# PCB1a_Adapter.net
KiCad netlist of a schematic drawn in EAGLE
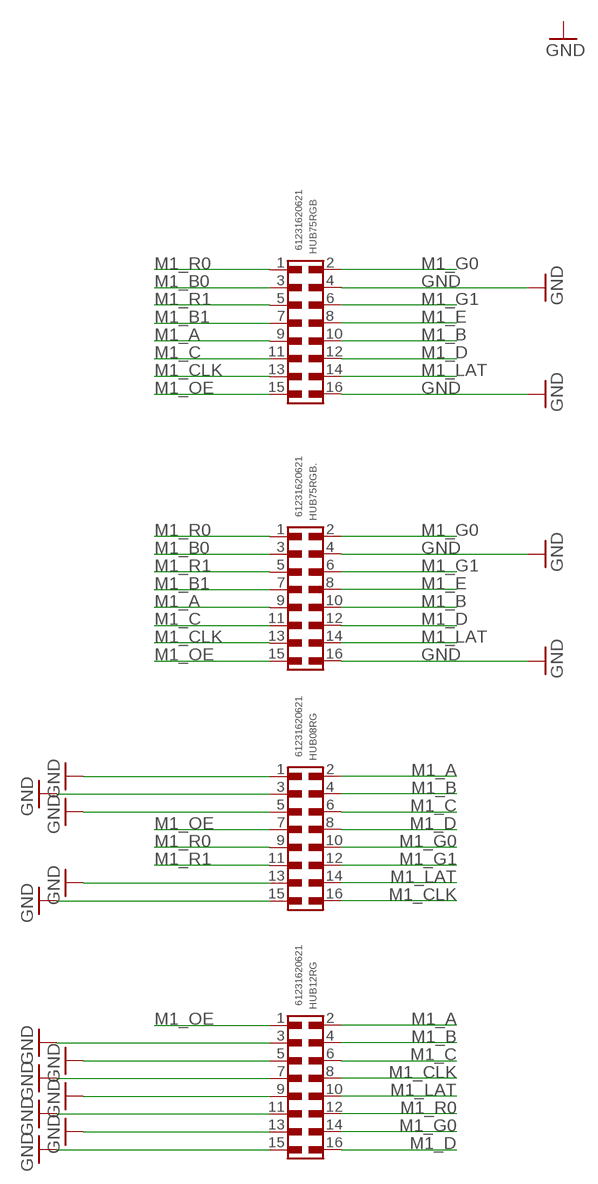
[diagram p0: schematic, sheet 1]

(export (version "E")
  (design (tool "Eeschema 10.0.6"))
  (components
    (comp (ref "HUB08RG")
      (value "61231620621")
      (footprint "eagle-import:61231620621")
      (libsource (lib "eagle-import") (part "6123XX20621_61231620621"))
    )
    (comp (ref "HUB12RG")
      (value "61231620621")
      (footprint "eagle-import:61231620621")
      (libsource (lib "eagle-import") (part "6123XX20621_61231620621"))
    )
    (comp (ref "HUB75RGB")
      (value "61231620621")
      (footprint "eagle-import:61231620621")
      (libsource (lib "eagle-import") (part "6123XX20621_61231620621"))
    )
    (comp (ref "HUB75RGB.")
      (value "61231620621")
      (footprint "eagle-import:61231620621")
      (libsource (lib "eagle-import") (part "6123XX20621_61231620621"))
    )
  )
  (nets
    (net (code "1") (name "/M1_A") (class "Default")
      (node (ref "HUB08RG") (pin "2") (pinfunction "2_2") (pintype "passive"))
      (node (ref "HUB12RG") (pin "2") (pinfunction "2_2") (pintype "passive"))
      (node (ref "HUB75RGB") (pin "9") (pinfunction "9_9") (pintype "passive"))
      (node (ref "HUB75RGB.") (pin "9") (pinfunction "9_9") (pintype "passive"))
    )
    (net (code "2") (name "/M1_B") (class "Default")
      (node (ref "HUB08RG") (pin "4") (pinfunction "4_4") (pintype "passive"))
      (node (ref "HUB12RG") (pin "4") (pinfunction "4_4") (pintype "passive"))
      (node (ref "HUB75RGB") (pin "10") (pinfunction "10_10") (pintype "passive"))
      (node (ref "HUB75RGB.") (pin "10") (pinfunction "10_10") (pintype "passive"))
    )
    (net (code "3") (name "/M1_B0") (class "Default")
      (node (ref "HUB75RGB") (pin "3") (pinfunction "3_3") (pintype "passive"))
      (node (ref "HUB75RGB.") (pin "3") (pinfunction "3_3") (pintype "passive"))
    )
    (net (code "4") (name "/M1_B1") (class "Default")
      (node (ref "HUB75RGB") (pin "7") (pinfunction "7_7") (pintype "passive"))
      (node (ref "HUB75RGB.") (pin "7") (pinfunction "7_7") (pintype "passive"))
    )
    (net (code "5") (name "/M1_C") (class "Default")
      (node (ref "HUB08RG") (pin "6") (pinfunction "6_6") (pintype "passive"))
      (node (ref "HUB12RG") (pin "6") (pinfunction "6_6") (pintype "passive"))
      (node (ref "HUB75RGB") (pin "11") (pinfunction "11_11") (pintype "passive"))
      (node (ref "HUB75RGB.") (pin "11") (pinfunction "11_11") (pintype "passive"))
    )
    (net (code "6") (name "/M1_CLK") (class "Default")
      (node (ref "HUB08RG") (pin "16") (pinfunction "16_16") (pintype "passive"))
      (node (ref "HUB12RG") (pin "8") (pinfunction "8_8") (pintype "passive"))
      (node (ref "HUB75RGB") (pin "13") (pinfunction "13_13") (pintype "passive"))
      (node (ref "HUB75RGB.") (pin "13") (pinfunction "13_13") (pintype "passive"))
    )
    (net (code "7") (name "/M1_D") (class "Default")
      (node (ref "HUB08RG") (pin "8") (pinfunction "8_8") (pintype "passive"))
      (node (ref "HUB12RG") (pin "16") (pinfunction "16_16") (pintype "passive"))
      (node (ref "HUB75RGB") (pin "12") (pinfunction "12_12") (pintype "passive"))
      (node (ref "HUB75RGB.") (pin "12") (pinfunction "12_12") (pintype "passive"))
    )
    (net (code "8") (name "/M1_E") (class "Default")
      (node (ref "HUB75RGB") (pin "8") (pinfunction "8_8") (pintype "passive"))
      (node (ref "HUB75RGB.") (pin "8") (pinfunction "8_8") (pintype "passive"))
    )
    (net (code "9") (name "/M1_G0") (class "Default")
      (node (ref "HUB08RG") (pin "10") (pinfunction "10_10") (pintype "passive"))
      (node (ref "HUB12RG") (pin "14") (pinfunction "14_14") (pintype "passive"))
      (node (ref "HUB75RGB") (pin "2") (pinfunction "2_2") (pintype "passive"))
      (node (ref "HUB75RGB.") (pin "2") (pinfunction "2_2") (pintype "passive"))
    )
    (net (code "10") (name "/M1_G1") (class "Default")
      (node (ref "HUB08RG") (pin "12") (pinfunction "12_12") (pintype "passive"))
      (node (ref "HUB75RGB") (pin "6") (pinfunction "6_6") (pintype "passive"))
      (node (ref "HUB75RGB.") (pin "6") (pinfunction "6_6") (pintype "passive"))
    )
    (net (code "11") (name "/M1_LAT") (class "Default")
      (node (ref "HUB08RG") (pin "14") (pinfunction "14_14") (pintype "passive"))
      (node (ref "HUB12RG") (pin "10") (pinfunction "10_10") (pintype "passive"))
      (node (ref "HUB75RGB") (pin "14") (pinfunction "14_14") (pintype "passive"))
      (node (ref "HUB75RGB.") (pin "14") (pinfunction "14_14") (pintype "passive"))
    )
    (net (code "12") (name "/M1_OE") (class "Default")
      (node (ref "HUB08RG") (pin "7") (pinfunction "7_7") (pintype "passive"))
      (node (ref "HUB12RG") (pin "1") (pinfunction "1_1") (pintype "passive"))
      (node (ref "HUB75RGB") (pin "15") (pinfunction "15_15") (pintype "passive"))
      (node (ref "HUB75RGB.") (pin "15") (pinfunction "15_15") (pintype "passive"))
    )
    (net (code "13") (name "/M1_R0") (class "Default")
      (node (ref "HUB08RG") (pin "9") (pinfunction "9_9") (pintype "passive"))
      (node (ref "HUB12RG") (pin "12") (pinfunction "12_12") (pintype "passive"))
      (node (ref "HUB75RGB") (pin "1") (pinfunction "1_1") (pintype "passive"))
      (node (ref "HUB75RGB.") (pin "1") (pinfunction "1_1") (pintype "passive"))
    )
    (net (code "14") (name "/M1_R1") (class "Default")
      (node (ref "HUB08RG") (pin "11") (pinfunction "11_11") (pintype "passive"))
      (node (ref "HUB75RGB") (pin "5") (pinfunction "5_5") (pintype "passive"))
      (node (ref "HUB75RGB.") (pin "5") (pinfunction "5_5") (pintype "passive"))
    )
    (net (code "15") (name "GND") (class "Default")
      (node (ref "HUB08RG") (pin "1") (pinfunction "1_1") (pintype "passive"))
      (node (ref "HUB08RG") (pin "13") (pinfunction "13_13") (pintype "passive"))
      (node (ref "HUB08RG") (pin "15") (pinfunction "15_15") (pintype "passive"))
      (node (ref "HUB08RG") (pin "3") (pinfunction "3_3") (pintype "passive"))
      (node (ref "HUB08RG") (pin "5") (pinfunction "5_5") (pintype "passive"))
      (node (ref "HUB12RG") (pin "11") (pinfunction "11_11") (pintype "passive"))
      (node (ref "HUB12RG") (pin "13") (pinfunction "13_13") (pintype "passive"))
      (node (ref "HUB12RG") (pin "15") (pinfunction "15_15") (pintype "passive"))
      (node (ref "HUB12RG") (pin "3") (pinfunction "3_3") (pintype "passive"))
      (node (ref "HUB12RG") (pin "5") (pinfunction "5_5") (pintype "passive"))
      (node (ref "HUB12RG") (pin "7") (pinfunction "7_7") (pintype "passive"))
      (node (ref "HUB12RG") (pin "9") (pinfunction "9_9") (pintype "passive"))
      (node (ref "HUB75RGB") (pin "16") (pinfunction "16_16") (pintype "passive"))
      (node (ref "HUB75RGB") (pin "4") (pinfunction "4_4") (pintype "passive"))
      (node (ref "HUB75RGB.") (pin "16") (pinfunction "16_16") (pintype "passive"))
      (node (ref "HUB75RGB.") (pin "4") (pinfunction "4_4") (pintype "passive"))
    )
  )
)
